# sameh.net
KiCad netlist of a schematic drawn in EAGLE
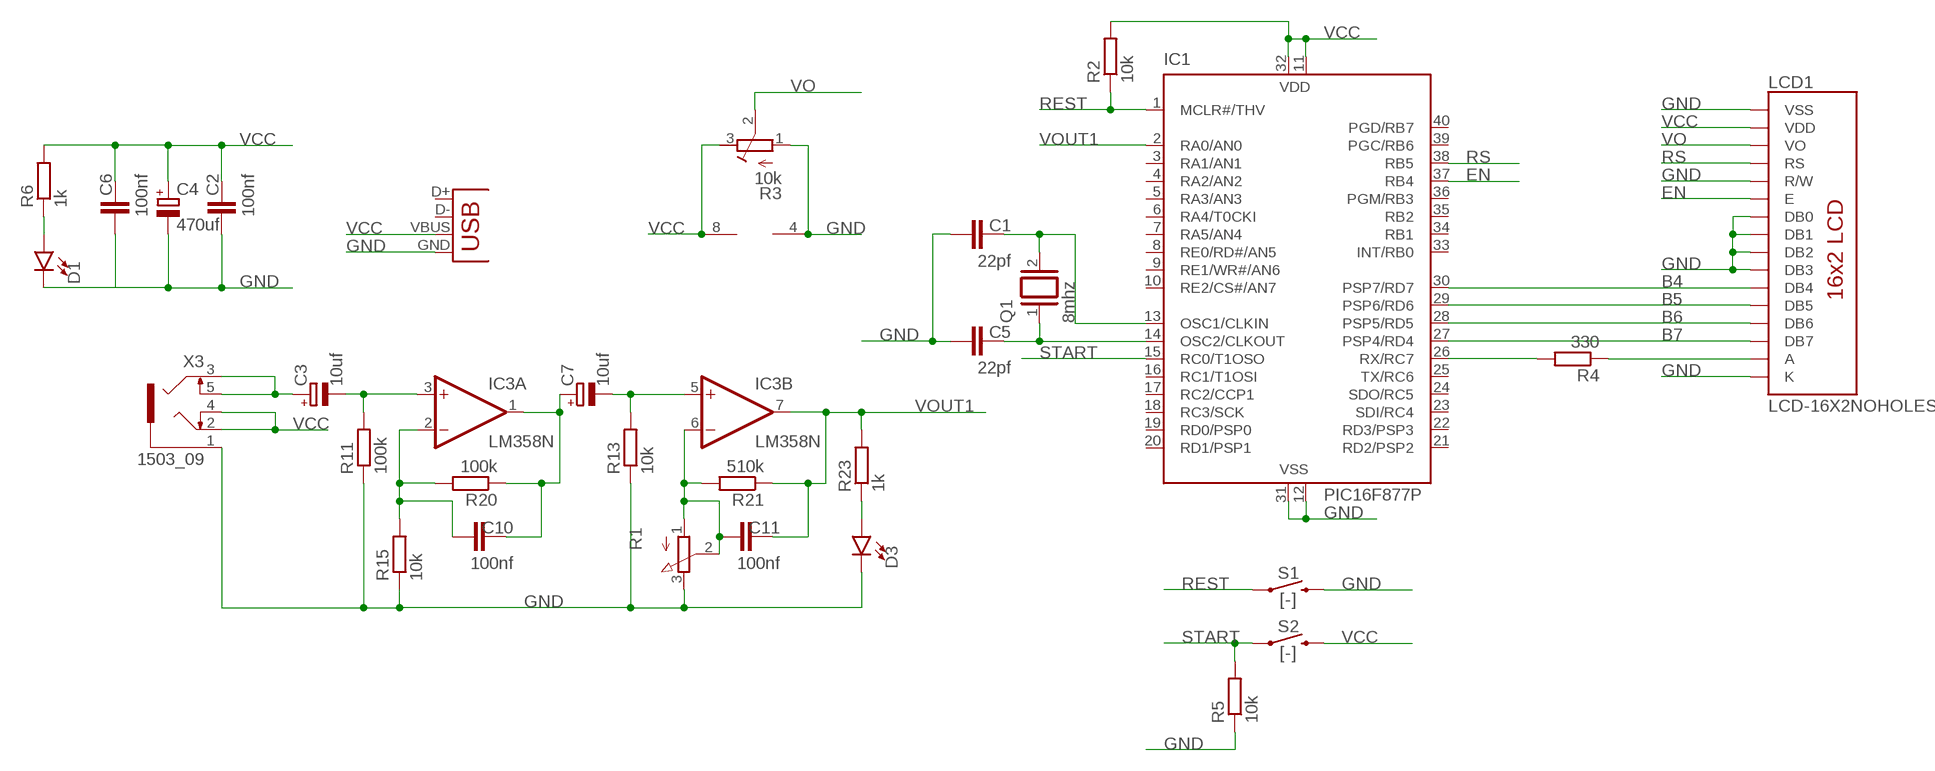
[diagram p0: schematic, sheet 1]

(export (version "E")
  (design (tool "Eeschema 10.0.6"))
  (components
    (comp (ref "C1")
      (value "22pf")
      (footprint "eagle-import:C050-030X075")
      (libsource (lib "eagle-import") (part "C-EU050-030X075"))
    )
    (comp (ref "C2")
      (value "100nf")
      (footprint "eagle-import:C050-030X075")
      (libsource (lib "eagle-import") (part "C-EU050-030X075"))
    )
    (comp (ref "C3")
      (value "10uf")
      (footprint "eagle-import:E2-5")
      (libsource (lib "eagle-import") (part "CPOL-EUE2-5"))
    )
    (comp (ref "C4")
      (value "470uf")
      (footprint "eagle-import:E3,5-8")
      (libsource (lib "eagle-import") (part "CPOL-EUE3.5-8"))
    )
    (comp (ref "C5")
      (value "22pf")
      (footprint "eagle-import:C050-030X075")
      (libsource (lib "eagle-import") (part "C-EU050-030X075"))
    )
    (comp (ref "C6")
      (value "100nf")
      (footprint "eagle-import:C050-030X075")
      (libsource (lib "eagle-import") (part "C-EU050-030X075"))
    )
    (comp (ref "C7")
      (value "10uf")
      (footprint "eagle-import:E2-5")
      (libsource (lib "eagle-import") (part "CPOL-EUE2-5"))
    )
    (comp (ref "C10")
      (value "100nf")
      (footprint "eagle-import:C050-030X075")
      (libsource (lib "eagle-import") (part "C-EU050-030X075"))
    )
    (comp (ref "C11")
      (value "100nf")
      (footprint "eagle-import:C050-030X075")
      (libsource (lib "eagle-import") (part "C-EU050-030X075"))
    )
    (comp (ref "D1")
      (value "LED5MM")
      (footprint "eagle-import:LED_5MM")
      (libsource (lib "eagle-import") (part "LED5MM"))
    )
    (comp (ref "D3")
      (value "LED5MM")
      (footprint "eagle-import:LED_5MM")
      (libsource (lib "eagle-import") (part "LED5MM"))
    )
    (comp (ref "IC1")
      (value "PIC16F877P")
      (footprint "eagle-import:DIL40")
      (libsource (lib "eagle-import") (part "PIC16F87P7"))
    )
    (comp (ref "IC3")
      (value "LM358N")
      (footprint "eagle-import:DIL08")
      (libsource (lib "eagle-import") (part "LM358N"))
    )
    (comp (ref "LCD1")
      (value "LCD-16X2NOHOLES")
      (footprint "eagle-import:LCD-16X2_NOHOLESNOSILK")
      (libsource (lib "eagle-import") (part "LCD-16X2NOHOLES"))
    )
    (comp (ref "Q1")
      (value "8mhz")
      (footprint "eagle-import:QS")
      (libsource (lib "eagle-import") (part "XTAL/S"))
    )
    (comp (ref "R1")
      (value "3RP/1610N")
      (footprint "eagle-import:3RP_1610N")
      (libsource (lib "eagle-import") (part "3RP/1610N"))
    )
    (comp (ref "R2")
      (value "10k")
      (footprint "eagle-import:0207_10")
      (libsource (lib "eagle-import") (part "R-EU_0207/10"))
    )
    (comp (ref "R3")
      (value "10k")
      (footprint "eagle-import:RTRIM64W")
      (libsource (lib "eagle-import") (part "R-TRIMM64W"))
    )
    (comp (ref "R4")
      (value "330")
      (footprint "eagle-import:0207_10")
      (libsource (lib "eagle-import") (part "R-EU_0207/10"))
    )
    (comp (ref "R5")
      (value "10k")
      (footprint "eagle-import:0207_10")
      (libsource (lib "eagle-import") (part "R-EU_0207/10"))
    )
    (comp (ref "R6")
      (value "1k")
      (footprint "eagle-import:0207_10")
      (libsource (lib "eagle-import") (part "R-EU_0207/10"))
    )
    (comp (ref "R11")
      (value "100k")
      (footprint "eagle-import:0207_10")
      (libsource (lib "eagle-import") (part "R-EU_0207/10"))
    )
    (comp (ref "R13")
      (value "10k")
      (footprint "eagle-import:0207_10")
      (libsource (lib "eagle-import") (part "R-EU_0207/10"))
    )
    (comp (ref "R15")
      (value "10k")
      (footprint "eagle-import:0207_10")
      (libsource (lib "eagle-import") (part "R-EU_0207/10"))
    )
    (comp (ref "R20")
      (value "100k")
      (footprint "eagle-import:0207_10")
      (libsource (lib "eagle-import") (part "R-EU_0207/10"))
    )
    (comp (ref "R21")
      (value "510k")
      (footprint "eagle-import:0207_10")
      (libsource (lib "eagle-import") (part "R-EU_0207/10"))
    )
    (comp (ref "R23")
      (value "1k")
      (footprint "eagle-import:0207_10")
      (libsource (lib "eagle-import") (part "R-EU_0207/10"))
    )
    (comp (ref "S1")
      (value "[-]")
      (footprint "eagle-import:TACTILE_SWITCH_PTH_6.0MM")
      (libsource (lib "eagle-import") (part "MOMENTARY-SWITCH-SPST-PTH-6.0MM"))
    )
    (comp (ref "S2")
      (value "[-]")
      (footprint "eagle-import:TACTILE_SWITCH_PTH_6.0MM")
      (libsource (lib "eagle-import") (part "MOMENTARY-SWITCH-SPST-PTH-6.0MM"))
    )
    (comp (ref "X2")
      (value "USB-B-H")
      (footprint "eagle-import:USB-B-H")
      (libsource (lib "eagle-import") (part "USB-B-H"))
    )
    (comp (ref "X3")
      (value "1503_09")
      (footprint "eagle-import:1503_09")
      (libsource (lib "eagle-import") (part "1503_09"))
    )
  )
  (nets
    (net (code "1") (name "/B4") (class "Default")
      (node (ref "IC1") (pin "30") (pinfunction "PSP7/RD7_30") (pintype "bidirectional"))
      (node (ref "LCD1") (pin "11") (pinfunction "DB4_11") (pintype "bidirectional"))
    )
    (net (code "2") (name "/B5") (class "Default")
      (node (ref "IC1") (pin "29") (pinfunction "PSP6/RD6_29") (pintype "bidirectional"))
      (node (ref "LCD1") (pin "12") (pinfunction "DB5_12") (pintype "bidirectional"))
    )
    (net (code "3") (name "/B6") (class "Default")
      (node (ref "IC1") (pin "28") (pinfunction "PSP5/RD5_28") (pintype "bidirectional"))
      (node (ref "LCD1") (pin "13") (pinfunction "DB6_13") (pintype "bidirectional"))
    )
    (net (code "4") (name "/B7") (class "Default")
      (node (ref "IC1") (pin "27") (pinfunction "PSP4/RD4_27") (pintype "bidirectional"))
      (node (ref "LCD1") (pin "14") (pinfunction "DB7_14") (pintype "bidirectional"))
    )
    (net (code "5") (name "/EN") (class "Default")
      (node (ref "IC1") (pin "37") (pinfunction "RB4_37") (pintype "bidirectional"))
      (node (ref "LCD1") (pin "6") (pinfunction "E_6") (pintype "input"))
    )
    (net (code "6") (name "/GND") (class "Default")
      (node (ref "C1") (pin "1") (pinfunction "1_1") (pintype "passive"))
      (node (ref "C2") (pin "1") (pinfunction "1_1") (pintype "passive"))
      (node (ref "C4") (pin "-") (pinfunction "-_-") (pintype "passive"))
      (node (ref "C5") (pin "1") (pinfunction "1_1") (pintype "passive"))
      (node (ref "C6") (pin "1") (pinfunction "1_1") (pintype "passive"))
      (node (ref "D1") (pin "K") (pinfunction "C_K") (pintype "passive"))
      (node (ref "D3") (pin "K") (pinfunction "C_K") (pintype "passive"))
      (node (ref "IC1") (pin "12") (pinfunction "VSS_12") (pintype "power_in"))
      (node (ref "IC1") (pin "31") (pinfunction "VSS_31") (pintype "power_in"))
      (node (ref "IC3") (pin "4") (pinfunction "V-_4") (pintype "power_in"))
      (node (ref "LCD1") (pin "1") (pinfunction "VSS_1") (pintype "power_in"))
      (node (ref "LCD1") (pin "10") (pinfunction "DB3_10") (pintype "bidirectional"))
      (node (ref "LCD1") (pin "16") (pinfunction "K_16") (pintype "power_in"))
      (node (ref "LCD1") (pin "5") (pinfunction "R/W_5") (pintype "input"))
      (node (ref "LCD1") (pin "7") (pinfunction "DB0_7") (pintype "bidirectional"))
      (node (ref "LCD1") (pin "8") (pinfunction "DB1_8") (pintype "bidirectional"))
      (node (ref "LCD1") (pin "9") (pinfunction "DB2_9") (pintype "bidirectional"))
      (node (ref "R1") (pin "3") (pinfunction "E_3") (pintype "passive"))
      (node (ref "R11") (pin "1") (pinfunction "1_1") (pintype "passive"))
      (node (ref "R13") (pin "1") (pinfunction "1_1") (pintype "passive"))
      (node (ref "R15") (pin "1") (pinfunction "1_1") (pintype "passive"))
      (node (ref "R3") (pin "1") (pinfunction "A_1") (pintype "passive"))
      (node (ref "R5") (pin "1") (pinfunction "1_1") (pintype "passive"))
      (node (ref "S1") (pin "3") (pinfunction "2_3") (pintype "passive"))
      (node (ref "X2") (pin "GND") (pinfunction "GND_GND") (pintype "bidirectional"))
      (node (ref "X3") (pin "1") (pinfunction "1_1") (pintype "passive"))
    )
    (net (code "7") (name "/REST") (class "Default")
      (node (ref "IC1") (pin "1") (pinfunction "MCLR#/THV_1") (pintype "input"))
      (node (ref "R2") (pin "1") (pinfunction "1_1") (pintype "passive"))
      (node (ref "S1") (pin "1") (pinfunction "1_1") (pintype "passive"))
    )
    (net (code "8") (name "/RS") (class "Default")
      (node (ref "IC1") (pin "38") (pinfunction "RB5_38") (pintype "bidirectional"))
      (node (ref "LCD1") (pin "4") (pinfunction "RS_4") (pintype "input"))
    )
    (net (code "9") (name "/START") (class "Default")
      (node (ref "IC1") (pin "15") (pinfunction "RC0/T1OSO_15") (pintype "bidirectional"))
      (node (ref "R5") (pin "2") (pinfunction "2_2") (pintype "passive"))
      (node (ref "S2") (pin "1") (pinfunction "1_1") (pintype "passive"))
    )
    (net (code "10") (name "/VCC") (class "Default")
      (node (ref "C2") (pin "2") (pinfunction "2_2") (pintype "passive"))
      (node (ref "C4") (pin "+") (pinfunction "+_+") (pintype "passive"))
      (node (ref "C6") (pin "2") (pinfunction "2_2") (pintype "passive"))
      (node (ref "IC1") (pin "11") (pinfunction "VDD_11") (pintype "power_in"))
      (node (ref "IC1") (pin "32") (pinfunction "VDD_32") (pintype "power_in"))
      (node (ref "IC3") (pin "8") (pinfunction "V+_8") (pintype "power_in"))
      (node (ref "LCD1") (pin "2") (pinfunction "VDD_2") (pintype "power_in"))
      (node (ref "R2") (pin "2") (pinfunction "2_2") (pintype "passive"))
      (node (ref "R3") (pin "3") (pinfunction "E_3") (pintype "passive"))
      (node (ref "R6") (pin "2") (pinfunction "2_2") (pintype "passive"))
      (node (ref "S2") (pin "3") (pinfunction "2_3") (pintype "passive"))
      (node (ref "X2") (pin "VBUS") (pinfunction "VBUS_VBUS") (pintype "bidirectional"))
      (node (ref "X3") (pin "2") (pinfunction "2_2") (pintype "passive"))
      (node (ref "X3") (pin "4") (pinfunction "4_4") (pintype "passive"))
    )
    (net (code "11") (name "/VO") (class "Default")
      (node (ref "LCD1") (pin "3") (pinfunction "VO_3") (pintype "bidirectional"))
      (node (ref "R3") (pin "2") (pinfunction "S_2") (pintype "passive"))
    )
    (net (code "12") (name "/VOUT1") (class "Default")
      (node (ref "C11") (pin "2") (pinfunction "2_2") (pintype "passive"))
      (node (ref "IC1") (pin "2") (pinfunction "RA0/AN0_2") (pintype "bidirectional"))
      (node (ref "IC3") (pin "7") (pinfunction "OUT_7") (pintype "output"))
      (node (ref "R21") (pin "1") (pinfunction "1_1") (pintype "passive"))
      (node (ref "R23") (pin "2") (pinfunction "2_2") (pintype "passive"))
    )
    (net (code "13") (name "Net-(C3-Pad+)") (class "Default")
      (node (ref "C3") (pin "+") (pinfunction "+_+") (pintype "passive"))
      (node (ref "X3") (pin "3") (pinfunction "3_3") (pintype "passive"))
      (node (ref "X3") (pin "5") (pinfunction "5_5") (pintype "passive"))
    )
    (net (code "14") (name "Net-(D1-PadA)") (class "Default")
      (node (ref "D1") (pin "A") (pinfunction "A_A") (pintype "passive"))
      (node (ref "R6") (pin "1") (pinfunction "1_1") (pintype "passive"))
    )
    (net (code "15") (name "Net-(D3-PadA)") (class "Default")
      (node (ref "D3") (pin "A") (pinfunction "A_A") (pintype "passive"))
      (node (ref "R23") (pin "1") (pinfunction "1_1") (pintype "passive"))
    )
    (net (code "16") (name "Net-(IC1-OSC1{slash}CLKIN)") (class "Default")
      (node (ref "C1") (pin "2") (pinfunction "2_2") (pintype "passive"))
      (node (ref "IC1") (pin "13") (pinfunction "OSC1/CLKIN_13") (pintype "input"))
      (node (ref "Q1") (pin "2") (pinfunction "2_2") (pintype "passive"))
    )
    (net (code "17") (name "Net-(IC1-OSC2{slash}CLKOUT)") (class "Default")
      (node (ref "C5") (pin "2") (pinfunction "2_2") (pintype "passive"))
      (node (ref "IC1") (pin "14") (pinfunction "OSC2/CLKOUT_14") (pintype "output"))
      (node (ref "Q1") (pin "1") (pinfunction "1_1") (pintype "passive"))
    )
    (net (code "18") (name "Net-(IC1-RX{slash}RC7)") (class "Default")
      (node (ref "IC1") (pin "26") (pinfunction "RX/RC7_26") (pintype "bidirectional"))
      (node (ref "R4") (pin "2") (pinfunction "2_2") (pintype "passive"))
    )
    (net (code "19") (name "Net-(IC3A-+IN)") (class "Default")
      (node (ref "C3") (pin "-") (pinfunction "-_-") (pintype "passive"))
      (node (ref "IC3") (pin "3") (pinfunction "+IN_3") (pintype "input"))
      (node (ref "R11") (pin "2") (pinfunction "2_2") (pintype "passive"))
    )
    (net (code "20") (name "Net-(IC3A--IN)") (class "Default")
      (node (ref "C10") (pin "1") (pinfunction "1_1") (pintype "passive"))
      (node (ref "IC3") (pin "2") (pinfunction "-IN_2") (pintype "input"))
      (node (ref "R15") (pin "2") (pinfunction "2_2") (pintype "passive"))
      (node (ref "R20") (pin "2") (pinfunction "2_2") (pintype "passive"))
    )
    (net (code "21") (name "Net-(IC3A-OUT)") (class "Default")
      (node (ref "C10") (pin "2") (pinfunction "2_2") (pintype "passive"))
      (node (ref "C7") (pin "+") (pinfunction "+_+") (pintype "passive"))
      (node (ref "IC3") (pin "1") (pinfunction "OUT_1") (pintype "output"))
      (node (ref "R20") (pin "1") (pinfunction "1_1") (pintype "passive"))
    )
    (net (code "22") (name "Net-(IC3B-+IN)") (class "Default")
      (node (ref "C7") (pin "-") (pinfunction "-_-") (pintype "passive"))
      (node (ref "IC3") (pin "5") (pinfunction "+IN_5") (pintype "input"))
      (node (ref "R13") (pin "2") (pinfunction "2_2") (pintype "passive"))
    )
    (net (code "23") (name "Net-(IC3B--IN)") (class "Default")
      (node (ref "C11") (pin "1") (pinfunction "1_1") (pintype "passive"))
      (node (ref "IC3") (pin "6") (pinfunction "-IN_6") (pintype "input"))
      (node (ref "R1") (pin "1") (pinfunction "A_1") (pintype "passive"))
      (node (ref "R1") (pin "2") (pinfunction "S_2") (pintype "passive"))
      (node (ref "R21") (pin "2") (pinfunction "2_2") (pintype "passive"))
    )
    (net (code "24") (name "Net-(LCD1-A)") (class "Default")
      (node (ref "LCD1") (pin "15") (pinfunction "A_15") (pintype "power_in"))
      (node (ref "R4") (pin "1") (pinfunction "1_1") (pintype "passive"))
    )
    (net (code "25") (name "unconnected-(IC1-INT{slash}RB0-Pad33)") (class "Default")
      (node (ref "IC1") (pin "33") (pinfunction "INT/RB0_33") (pintype "bidirectional"))
    )
    (net (code "26") (name "unconnected-(IC1-PGC{slash}RB6-Pad39)") (class "Default")
      (node (ref "IC1") (pin "39") (pinfunction "PGC/RB6_39") (pintype "bidirectional"))
    )
    (net (code "27") (name "unconnected-(IC1-PGD{slash}RB7-Pad40)") (class "Default")
      (node (ref "IC1") (pin "40") (pinfunction "PGD/RB7_40") (pintype "bidirectional"))
    )
    (net (code "28") (name "unconnected-(IC1-PGM{slash}RB3-Pad36)") (class "Default")
      (node (ref "IC1") (pin "36") (pinfunction "PGM/RB3_36") (pintype "bidirectional"))
    )
    (net (code "29") (name "unconnected-(IC1-RA1{slash}AN1-Pad3)") (class "Default")
      (node (ref "IC1") (pin "3") (pinfunction "RA1/AN1_3") (pintype "bidirectional"))
    )
    (net (code "30") (name "unconnected-(IC1-RA2{slash}AN2-Pad4)") (class "Default")
      (node (ref "IC1") (pin "4") (pinfunction "RA2/AN2_4") (pintype "bidirectional"))
    )
    (net (code "31") (name "unconnected-(IC1-RA3{slash}AN3-Pad5)") (class "Default")
      (node (ref "IC1") (pin "5") (pinfunction "RA3/AN3_5") (pintype "bidirectional"))
    )
    (net (code "32") (name "unconnected-(IC1-RA4{slash}T0CKI-Pad6)") (class "Default")
      (node (ref "IC1") (pin "6") (pinfunction "RA4/T0CKI_6") (pintype "bidirectional"))
    )
    (net (code "33") (name "unconnected-(IC1-RA5{slash}AN4-Pad7)") (class "Default")
      (node (ref "IC1") (pin "7") (pinfunction "RA5/AN4_7") (pintype "bidirectional"))
    )
    (net (code "34") (name "unconnected-(IC1-RB1-Pad34)") (class "Default")
      (node (ref "IC1") (pin "34") (pinfunction "RB1_34") (pintype "bidirectional"))
    )
    (net (code "35") (name "unconnected-(IC1-RB2-Pad35)") (class "Default")
      (node (ref "IC1") (pin "35") (pinfunction "RB2_35") (pintype "bidirectional"))
    )
    (net (code "36") (name "unconnected-(IC1-RC1{slash}T1OSI-Pad16)") (class "Default")
      (node (ref "IC1") (pin "16") (pinfunction "RC1/T1OSI_16") (pintype "bidirectional"))
    )
    (net (code "37") (name "unconnected-(IC1-RC2{slash}CCP1-Pad17)") (class "Default")
      (node (ref "IC1") (pin "17") (pinfunction "RC2/CCP1_17") (pintype "bidirectional"))
    )
    (net (code "38") (name "unconnected-(IC1-RC3{slash}SCK-Pad18)") (class "Default")
      (node (ref "IC1") (pin "18") (pinfunction "RC3/SCK_18") (pintype "bidirectional"))
    )
    (net (code "39") (name "unconnected-(IC1-RD0{slash}PSP0-Pad19)") (class "Default")
      (node (ref "IC1") (pin "19") (pinfunction "RD0/PSP0_19") (pintype "bidirectional"))
    )
    (net (code "40") (name "unconnected-(IC1-RD1{slash}PSP1-Pad20)") (class "Default")
      (node (ref "IC1") (pin "20") (pinfunction "RD1/PSP1_20") (pintype "bidirectional"))
    )
    (net (code "41") (name "unconnected-(IC1-RD2{slash}PSP2-Pad21)") (class "Default")
      (node (ref "IC1") (pin "21") (pinfunction "RD2/PSP2_21") (pintype "bidirectional"))
    )
    (net (code "42") (name "unconnected-(IC1-RD3{slash}PSP3-Pad22)") (class "Default")
      (node (ref "IC1") (pin "22") (pinfunction "RD3/PSP3_22") (pintype "bidirectional"))
    )
    (net (code "43") (name "unconnected-(IC1-RE0{slash}RD#{slash}AN5-Pad8)") (class "Default")
      (node (ref "IC1") (pin "8") (pinfunction "RE0/RD#/AN5_8") (pintype "bidirectional"))
    )
    (net (code "44") (name "unconnected-(IC1-RE1{slash}WR#{slash}AN6-Pad9)") (class "Default")
      (node (ref "IC1") (pin "9") (pinfunction "RE1/WR#/AN6_9") (pintype "bidirectional"))
    )
    (net (code "45") (name "unconnected-(IC1-RE2{slash}CS#{slash}AN7-Pad10)") (class "Default")
      (node (ref "IC1") (pin "10") (pinfunction "RE2/CS#/AN7_10") (pintype "bidirectional"))
    )
    (net (code "46") (name "unconnected-(IC1-SDI{slash}RC4-Pad23)") (class "Default")
      (node (ref "IC1") (pin "23") (pinfunction "SDI/RC4_23") (pintype "bidirectional"))
    )
    (net (code "47") (name "unconnected-(IC1-SDO{slash}RC5-Pad24)") (class "Default")
      (node (ref "IC1") (pin "24") (pinfunction "SDO/RC5_24") (pintype "bidirectional"))
    )
    (net (code "48") (name "unconnected-(IC1-TX{slash}RC6-Pad25)") (class "Default")
      (node (ref "IC1") (pin "25") (pinfunction "TX/RC6_25") (pintype "bidirectional"))
    )
    (net (code "49") (name "unconnected-(X2-PadD+)") (class "Default")
      (node (ref "X2") (pin "D+") (pinfunction "D+_D+") (pintype "bidirectional"))
    )
    (net (code "50") (name "unconnected-(X2-PadD-)") (class "Default")
      (node (ref "X2") (pin "D-") (pinfunction "D-_D-") (pintype "bidirectional"))
    )
  )
)
